# amp.net
KiCad netlist of a schematic drawn in EAGLE
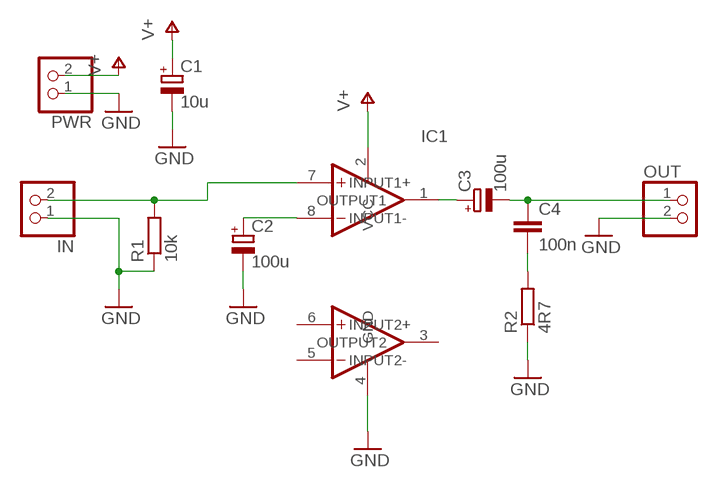
[diagram p0: schematic, sheet 1]

(export (version "E")
  (design (tool "Eeschema 10.0.6"))
  (components
    (comp (ref "C1")
      (value "10u")
      (footprint "eagle-import:E2,5-5")
      (libsource (lib "eagle-import") (part "CPOL-EUE2.5-5"))
    )
    (comp (ref "C2")
      (value "100u")
      (footprint "eagle-import:E2,5-5")
      (libsource (lib "eagle-import") (part "CPOL-EUE2.5-5"))
    )
    (comp (ref "C3")
      (value "100u")
      (footprint "eagle-import:E2,5-5")
      (libsource (lib "eagle-import") (part "CPOL-EUE2.5-5"))
    )
    (comp (ref "C4")
      (value "100n")
      (footprint "eagle-import:C0805")
      (libsource (lib "eagle-import") (part "C-EUC0805"))
    )
    (comp (ref "IC1")
      (value "TDA2822M")
      (footprint "eagle-import:DIL8")
      (libsource (lib "eagle-import") (part "TDA2822M"))
    )
    (comp (ref "IN")
      (value "PINHD-1X2")
      (footprint "eagle-import:1X02")
      (libsource (lib "eagle-import") (part "PINHD-1X2"))
    )
    (comp (ref "OUT")
      (value "PINHD-1X2")
      (footprint "eagle-import:1X02")
      (libsource (lib "eagle-import") (part "PINHD-1X2"))
    )
    (comp (ref "PWR")
      (value "PINHD-1X2")
      (footprint "eagle-import:1X02")
      (libsource (lib "eagle-import") (part "PINHD-1X2"))
    )
    (comp (ref "R1")
      (value "10k")
      (footprint "eagle-import:R0805")
      (libsource (lib "eagle-import") (part "R-EU_R0805"))
    )
    (comp (ref "R2")
      (value "4R7")
      (footprint "eagle-import:R0805")
      (libsource (lib "eagle-import") (part "R-EU_R0805"))
    )
  )
  (nets
    (net (code "1") (name "GND") (class "Default")
      (node (ref "C1") (pin "-") (pinfunction "-_-") (pintype "passive"))
      (node (ref "C2") (pin "-") (pinfunction "-_-") (pintype "passive"))
      (node (ref "IC1") (pin "4") (pinfunction "GND_4") (pintype "bidirectional"))
      (node (ref "IN") (pin "1") (pinfunction "1_1") (pintype "passive"))
      (node (ref "OUT") (pin "2") (pinfunction "2_2") (pintype "passive"))
      (node (ref "PWR") (pin "1") (pinfunction "1_1") (pintype "passive"))
      (node (ref "R1") (pin "1") (pinfunction "1_1") (pintype "passive"))
      (node (ref "R2") (pin "1") (pinfunction "1_1") (pintype "passive"))
    )
    (net (code "2") (name "Net-(C3-Pad-)") (class "Default")
      (node (ref "C3") (pin "-") (pinfunction "-_-") (pintype "passive"))
      (node (ref "C4") (pin "1") (pinfunction "1_1") (pintype "passive"))
      (node (ref "OUT") (pin "1") (pinfunction "1_1") (pintype "passive"))
    )
    (net (code "3") (name "Net-(C4-Pad2)") (class "Default")
      (node (ref "C4") (pin "2") (pinfunction "2_2") (pintype "passive"))
      (node (ref "R2") (pin "2") (pinfunction "2_2") (pintype "passive"))
    )
    (net (code "4") (name "Net-(IC1-INPUT1+)") (class "Default")
      (node (ref "IC1") (pin "7") (pinfunction "INPUT1+_7") (pintype "bidirectional"))
      (node (ref "IN") (pin "2") (pinfunction "2_2") (pintype "passive"))
      (node (ref "R1") (pin "2") (pinfunction "2_2") (pintype "passive"))
    )
    (net (code "5") (name "Net-(IC1-INPUT1-)") (class "Default")
      (node (ref "C2") (pin "+") (pinfunction "+_+") (pintype "passive"))
      (node (ref "IC1") (pin "8") (pinfunction "INPUT1-_8") (pintype "bidirectional"))
    )
    (net (code "6") (name "Net-(IC1-OUTPUT1)") (class "Default")
      (node (ref "C3") (pin "+") (pinfunction "+_+") (pintype "passive"))
      (node (ref "IC1") (pin "1") (pinfunction "OUTPUT1_1") (pintype "bidirectional"))
    )
    (net (code "7") (name "V+") (class "Default")
      (node (ref "C1") (pin "+") (pinfunction "+_+") (pintype "passive"))
      (node (ref "IC1") (pin "2") (pinfunction "VCC_2") (pintype "bidirectional"))
      (node (ref "PWR") (pin "2") (pinfunction "2_2") (pintype "passive"))
    )
    (net (code "8") (name "unconnected-(IC1-INPUT2+-Pad6)") (class "Default")
      (node (ref "IC1") (pin "6") (pinfunction "INPUT2+_6") (pintype "bidirectional"))
    )
    (net (code "9") (name "unconnected-(IC1-INPUT2--Pad5)") (class "Default")
      (node (ref "IC1") (pin "5") (pinfunction "INPUT2-_5") (pintype "bidirectional"))
    )
    (net (code "10") (name "unconnected-(IC1-OUTPUT2-Pad3)") (class "Default")
      (node (ref "IC1") (pin "3") (pinfunction "OUTPUT2_3") (pintype "bidirectional"))
    )
  )
)
